# design.net
KiCad netlist of a schematic drawn in Altium Designer
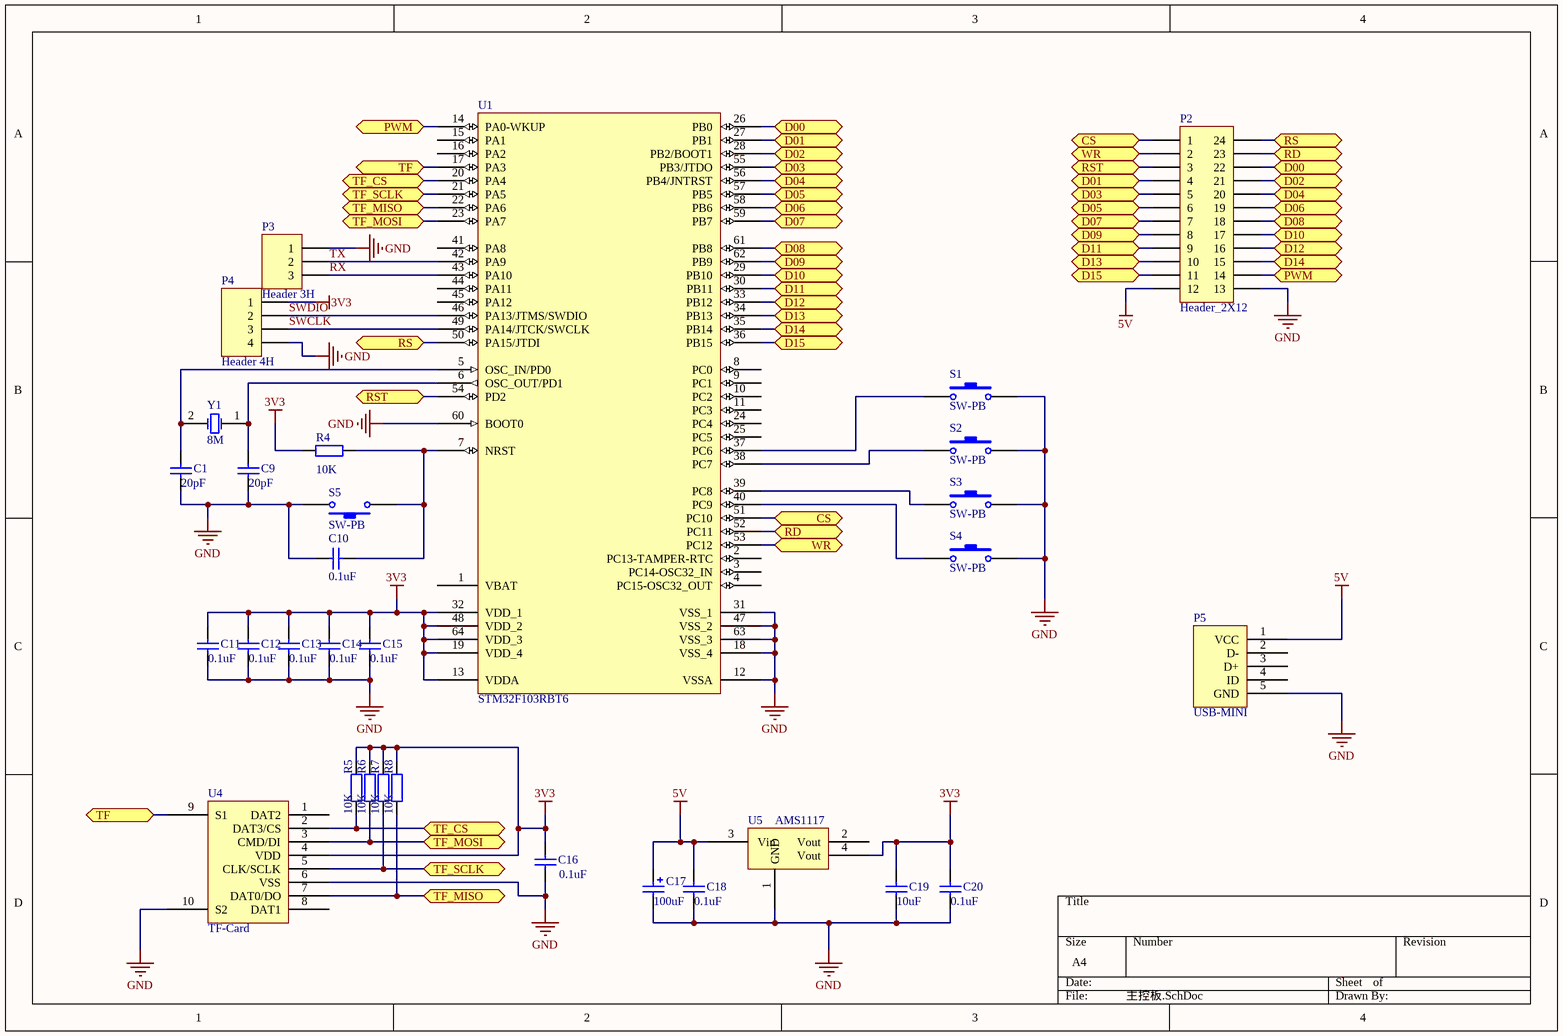
[diagram p0: 主控板.SchDoc]

(export (version "E")
  (design (tool "Eeschema 10.0.6"))
  (components
    (comp (ref "C1")
      (value "20pF")
      (footprint "6-0805_N")
      (description "Capacitor (Semiconductor SIM Model)")
      (fields (field (name "Comment") "Cap Semi") (field (name "PUBLISHER") "Altium Limited"))
      (libsource (lib "Miscellaneous Devices") (part "Cap Semi"))
    )
    (comp (ref "C9")
      (value "20pF")
      (footprint "6-0805_N")
      (description "Capacitor (Semiconductor SIM Model)")
      (fields (field (name "Comment") "Cap Semi") (field (name "PUBLISHER") "Altium Limited"))
      (libsource (lib "Miscellaneous Devices") (part "Cap Semi"))
    )
    (comp (ref "C10")
      (value "0.1uF")
      (footprint "1608[0603]")
      (description "Capacitor (Semiconductor SIM Model)")
      (fields (field (name "Comment") "Cap Semi") (field (name "PUBLISHER") "Altium Limited"))
      (libsource (lib "Miscellaneous Devices") (part "Cap Semi"))
    )
    (comp (ref "C11")
      (value "0.1uF")
      (footprint "1608[0603]")
      (description "Capacitor (Semiconductor SIM Model)")
      (fields (field (name "Comment") "Cap Semi") (field (name "PUBLISHER") "Altium Limited"))
      (libsource (lib "Miscellaneous Devices") (part "Cap Semi"))
    )
    (comp (ref "C12")
      (value "0.1uF")
      (footprint "1608[0603]")
      (description "Capacitor (Semiconductor SIM Model)")
      (fields (field (name "Comment") "Cap Semi") (field (name "PUBLISHER") "Altium Limited"))
      (libsource (lib "Miscellaneous Devices") (part "Cap Semi"))
    )
    (comp (ref "C13")
      (value "0.1uF")
      (footprint "1608[0603]")
      (description "Capacitor (Semiconductor SIM Model)")
      (fields (field (name "Comment") "Cap Semi") (field (name "PUBLISHER") "Altium Limited"))
      (libsource (lib "Miscellaneous Devices") (part "Cap Semi"))
    )
    (comp (ref "C14")
      (value "0.1uF")
      (footprint "1608[0603]")
      (description "Capacitor (Semiconductor SIM Model)")
      (fields (field (name "Comment") "Cap Semi") (field (name "PUBLISHER") "Altium Limited"))
      (libsource (lib "Miscellaneous Devices") (part "Cap Semi"))
    )
    (comp (ref "C15")
      (value "0.1uF")
      (footprint "1608[0603]")
      (description "Capacitor (Semiconductor SIM Model)")
      (fields (field (name "Comment") "Cap Semi") (field (name "PUBLISHER") "Altium Limited"))
      (libsource (lib "Miscellaneous Devices") (part "Cap Semi"))
    )
    (comp (ref "C16")
      (value "0.1uF")
      (footprint "1608[0603]")
      (description "Capacitor (Semiconductor SIM Model)")
      (fields (field (name "Comment") "Cap Semi") (field (name "PUBLISHER") "Altium Limited"))
      (libsource (lib "Miscellaneous Devices") (part "Cap Semi"))
    )
    (comp (ref "C17")
      (value "100uF")
      (footprint "3528")
      (description "Polarized Capacitor (Axial)")
      (fields (field (name "Comment") "Cap Pol2") (field (name "PUBLISHER") "Altium Limited"))
      (libsource (lib "Miscellaneous Devices") (part "Cap Pol2"))
    )
    (comp (ref "C18")
      (value "0.1uF")
      (footprint "1608[0603]")
      (description "Capacitor (Semiconductor SIM Model)")
      (fields (field (name "Comment") "Cap Semi") (field (name "PUBLISHER") "Altium Limited"))
      (libsource (lib "Miscellaneous Devices") (part "Cap Semi"))
    )
    (comp (ref "C19")
      (value "10uF")
      (footprint "1608[0603]")
      (description "Capacitor (Semiconductor SIM Model)")
      (fields (field (name "Comment") "Cap Semi") (field (name "PUBLISHER") "Altium Limited"))
      (libsource (lib "Miscellaneous Devices") (part "Cap Semi"))
    )
    (comp (ref "C20")
      (value "0.1uF")
      (footprint "1608[0603]")
      (description "Capacitor (Semiconductor SIM Model)")
      (fields (field (name "Comment") "Cap Semi") (field (name "PUBLISHER") "Altium Limited"))
      (libsource (lib "Miscellaneous Devices") (part "Cap Semi"))
    )
    (comp (ref "P2") (value "Header_2X12") (footprint "HDR2X12") (libsource (lib "元件") (part "Header_2X12")))
    (comp (ref "P3")
      (value "Header 3H")
      (footprint "HDR1X3H")
      (description "Header, 3-Pin, Right Angle")
      (fields (field (name "PUBLISHER") "Altium Limited"))
      (libsource (lib "Miscellaneous Connectors") (part "Header 3H"))
    )
    (comp (ref "P4")
      (value "Header 4H")
      (footprint "HDR1X4H")
      (description "Header, 4-Pin, Right Angle")
      (fields (field (name "PUBLISHER") "Altium Limited"))
      (libsource (lib "Miscellaneous Connectors") (part "Header 4H"))
    )
    (comp (ref "P5")
      (value "USB-MINI")
      (footprint "USB-MINI")
      (description "USB接口")
      (libsource (lib "元件") (part "USB-MINI"))
    )
    (comp (ref "R4")
      (value "10K")
      (footprint "1608[0603]")
      (description "Resistor")
      (fields (field (name "Comment") "Res2") (field (name "PUBLISHER") "Altium Limited"))
      (libsource (lib "") (part "Res2_1"))
    )
    (comp (ref "R5")
      (value "10K")
      (footprint "1608[0603]")
      (description "Resistor")
      (fields (field (name "Comment") "Res2") (field (name "PUBLISHER") "Altium Limited"))
      (libsource (lib "Miscellaneous Devices") (part "Res2"))
    )
    (comp (ref "R6")
      (value "10K")
      (footprint "1608[0603]")
      (description "Resistor")
      (fields (field (name "Comment") "Res2") (field (name "PUBLISHER") "Altium Limited"))
      (libsource (lib "Miscellaneous Devices") (part "Res2"))
    )
    (comp (ref "R7")
      (value "10K")
      (footprint "1608[0603]")
      (description "Resistor")
      (fields (field (name "Comment") "Res2") (field (name "PUBLISHER") "Altium Limited"))
      (libsource (lib "Miscellaneous Devices") (part "Res2"))
    )
    (comp (ref "R8")
      (value "10K")
      (footprint "1608[0603]")
      (description "Resistor")
      (fields (field (name "Comment") "Res2") (field (name "PUBLISHER") "Altium Limited"))
      (libsource (lib "Miscellaneous Devices") (part "Res2"))
    )
    (comp (ref "S1")
      (value "SW-PB")
      (footprint "SW-SMD")
      (description "Switch")
      (fields (field (name "PUBLISHER") "Altium Limited"))
      (libsource (lib "Miscellaneous Devices") (part "SW-PB"))
    )
    (comp (ref "S2")
      (value "SW-PB")
      (footprint "SW-SMD")
      (description "Switch")
      (fields (field (name "PUBLISHER") "Altium Limited"))
      (libsource (lib "Miscellaneous Devices") (part "SW-PB"))
    )
    (comp (ref "S3")
      (value "SW-PB")
      (footprint "SW-SMD")
      (description "Switch")
      (fields (field (name "PUBLISHER") "Altium Limited"))
      (libsource (lib "Miscellaneous Devices") (part "SW-PB"))
    )
    (comp (ref "S4")
      (value "SW-PB")
      (footprint "SW-SMD")
      (description "Switch")
      (fields (field (name "PUBLISHER") "Altium Limited"))
      (libsource (lib "Miscellaneous Devices") (part "SW-PB"))
    )
    (comp (ref "S5")
      (value "SW-PB")
      (footprint "SW-SMD")
      (description "Switch")
      (fields (field (name "PUBLISHER") "Altium Limited"))
      (libsource (lib "Miscellaneous Devices") (part "SW-PB"))
    )
    (comp (ref "U1")
      (value "STM32F103RBT6")
      (footprint "LQFP64_N")
      (description "STM32 ARM-based 32-bit MCU with 128 Kbytes Flash, 64-pin LQFP, Industrial Temperature")
      (fields (field (name "PUBLISHER") "Altium Limited"))
      (libsource (lib "ST Microcontroller 32-Bit STM32") (part "STM32F103RBT6"))
    )
    (comp (ref "U4")
      (value "TF-Card")
      (footprint "TF-Card")
      (description "TF存储卡")
      (libsource (lib "元件") (part "TF-Card"))
    )
    (comp (ref "U5")
      (value "AMS1117")
      (footprint "SOT223")
      (description "稳压IC")
      (libsource (lib "元件") (part "AMS1117"))
    )
    (comp (ref "Y1")
      (value "8M")
      (footprint "XTAL - duplicate")
      (description "Crystal Oscillator")
      (fields (field (name "PUBLISHER") "Altium Limited"))
      (libsource (lib "Miscellaneous Devices") (part "XTAL"))
    )
  )
  (nets
    (net (code "1") (name "/CS") (class "Default")
      (node (ref "P2") (pin "1") (pinfunction "1_1") (pintype "passive"))
      (node (ref "U1") (pin "51") (pinfunction "PC10_51") (pintype "bidirectional"))
    )
    (net (code "2") (name "/D00") (class "Default")
      (node (ref "P2") (pin "22") (pinfunction "22_22") (pintype "passive"))
      (node (ref "U1") (pin "26") (pinfunction "PB0_26") (pintype "bidirectional"))
    )
    (net (code "3") (name "/D01") (class "Default")
      (node (ref "P2") (pin "4") (pinfunction "4_4") (pintype "passive"))
      (node (ref "U1") (pin "27") (pinfunction "PB1_27") (pintype "bidirectional"))
    )
    (net (code "4") (name "/D02") (class "Default")
      (node (ref "P2") (pin "21") (pinfunction "21_21") (pintype "passive"))
      (node (ref "U1") (pin "28") (pinfunction "PB2/BOOT1_28") (pintype "bidirectional"))
    )
    (net (code "5") (name "/D03") (class "Default")
      (node (ref "P2") (pin "5") (pinfunction "5_5") (pintype "passive"))
      (node (ref "U1") (pin "55") (pinfunction "PB3/JTDO_55") (pintype "bidirectional"))
    )
    (net (code "6") (name "/D04") (class "Default")
      (node (ref "P2") (pin "20") (pinfunction "20_20") (pintype "passive"))
      (node (ref "U1") (pin "56") (pinfunction "PB4/JNTRST_56") (pintype "bidirectional"))
    )
    (net (code "7") (name "/D05") (class "Default")
      (node (ref "P2") (pin "6") (pinfunction "6_6") (pintype "passive"))
      (node (ref "U1") (pin "57") (pinfunction "PB5_57") (pintype "bidirectional"))
    )
    (net (code "8") (name "/D06") (class "Default")
      (node (ref "P2") (pin "19") (pinfunction "19_19") (pintype "passive"))
      (node (ref "U1") (pin "58") (pinfunction "PB6_58") (pintype "bidirectional"))
    )
    (net (code "9") (name "/D07") (class "Default")
      (node (ref "P2") (pin "7") (pinfunction "7_7") (pintype "passive"))
      (node (ref "U1") (pin "59") (pinfunction "PB7_59") (pintype "bidirectional"))
    )
    (net (code "10") (name "/D08") (class "Default")
      (node (ref "P2") (pin "18") (pinfunction "18_18") (pintype "passive"))
      (node (ref "U1") (pin "61") (pinfunction "PB8_61") (pintype "bidirectional"))
    )
    (net (code "11") (name "/D09") (class "Default")
      (node (ref "P2") (pin "8") (pinfunction "8_8") (pintype "passive"))
      (node (ref "U1") (pin "62") (pinfunction "PB9_62") (pintype "bidirectional"))
    )
    (net (code "12") (name "/D10") (class "Default")
      (node (ref "P2") (pin "17") (pinfunction "17_17") (pintype "passive"))
      (node (ref "U1") (pin "29") (pinfunction "PB10_29") (pintype "bidirectional"))
    )
    (net (code "13") (name "/D11") (class "Default")
      (node (ref "P2") (pin "9") (pinfunction "9_9") (pintype "passive"))
      (node (ref "U1") (pin "30") (pinfunction "PB11_30") (pintype "bidirectional"))
    )
    (net (code "14") (name "/D12") (class "Default")
      (node (ref "P2") (pin "16") (pinfunction "16_16") (pintype "passive"))
      (node (ref "U1") (pin "33") (pinfunction "PB12_33") (pintype "bidirectional"))
    )
    (net (code "15") (name "/D13") (class "Default")
      (node (ref "P2") (pin "10") (pinfunction "10_10") (pintype "passive"))
      (node (ref "U1") (pin "34") (pinfunction "PB13_34") (pintype "bidirectional"))
    )
    (net (code "16") (name "/D14") (class "Default")
      (node (ref "P2") (pin "15") (pinfunction "15_15") (pintype "passive"))
      (node (ref "U1") (pin "35") (pinfunction "PB14_35") (pintype "bidirectional"))
    )
    (net (code "17") (name "/D15") (class "Default")
      (node (ref "P2") (pin "11") (pinfunction "11_11") (pintype "passive"))
      (node (ref "U1") (pin "36") (pinfunction "PB15_36") (pintype "bidirectional"))
    )
    (net (code "18") (name "/PWM") (class "Default")
      (node (ref "P2") (pin "14") (pinfunction "14_14") (pintype "passive"))
      (node (ref "U1") (pin "14") (pinfunction "PA0-WKUP_14") (pintype "bidirectional"))
    )
    (net (code "19") (name "/RD") (class "Default")
      (node (ref "P2") (pin "23") (pinfunction "23_23") (pintype "passive"))
      (node (ref "U1") (pin "52") (pinfunction "PC11_52") (pintype "bidirectional"))
    )
    (net (code "20") (name "/RS") (class "Default")
      (node (ref "P2") (pin "24") (pinfunction "24_24") (pintype "passive"))
      (node (ref "U1") (pin "50") (pinfunction "PA15/JTDI_50") (pintype "bidirectional"))
    )
    (net (code "21") (name "/RST") (class "Default")
      (node (ref "P2") (pin "3") (pinfunction "3_3") (pintype "passive"))
      (node (ref "U1") (pin "54") (pinfunction "PD2_54") (pintype "bidirectional"))
    )
    (net (code "22") (name "/RX") (class "Default")
      (node (ref "P3") (pin "3") (pinfunction "3_3") (pintype "passive"))
      (node (ref "U1") (pin "43") (pinfunction "PA10_43") (pintype "bidirectional"))
    )
    (net (code "23") (name "/SWCLK") (class "Default")
      (node (ref "P4") (pin "3") (pinfunction "3_3") (pintype "passive"))
      (node (ref "U1") (pin "49") (pinfunction "PA14/JTCK/SWCLK_49") (pintype "bidirectional"))
    )
    (net (code "24") (name "/SWDIO") (class "Default")
      (node (ref "P4") (pin "2") (pinfunction "2_2") (pintype "passive"))
      (node (ref "U1") (pin "46") (pinfunction "PA13/JTMS/SWDIO_46") (pintype "bidirectional"))
    )
    (net (code "25") (name "/TF") (class "Default")
      (node (ref "U1") (pin "17") (pinfunction "PA3_17") (pintype "bidirectional"))
      (node (ref "U4") (pin "9") (pinfunction "S1_9") (pintype "passive"))
    )
    (net (code "26") (name "/TF_CS") (class "Default")
      (node (ref "R5") (pin "1") (pinfunction "1_1") (pintype "passive"))
      (node (ref "U1") (pin "20") (pinfunction "PA4_20") (pintype "bidirectional"))
      (node (ref "U4") (pin "2") (pinfunction "DAT3/CS_2") (pintype "passive"))
    )
    (net (code "27") (name "/TF_MISO") (class "Default")
      (node (ref "R8") (pin "1") (pinfunction "1_1") (pintype "passive"))
      (node (ref "U1") (pin "22") (pinfunction "PA6_22") (pintype "bidirectional"))
      (node (ref "U4") (pin "7") (pinfunction "DAT0/DO_7") (pintype "passive"))
    )
    (net (code "28") (name "/TF_MOSI") (class "Default")
      (node (ref "R6") (pin "1") (pinfunction "1_1") (pintype "passive"))
      (node (ref "U1") (pin "23") (pinfunction "PA7_23") (pintype "bidirectional"))
      (node (ref "U4") (pin "3") (pinfunction "CMD/DI_3") (pintype "passive"))
    )
    (net (code "29") (name "/TF_SCLK") (class "Default")
      (node (ref "R7") (pin "1") (pinfunction "1_1") (pintype "passive"))
      (node (ref "U1") (pin "21") (pinfunction "PA5_21") (pintype "bidirectional"))
      (node (ref "U4") (pin "5") (pinfunction "CLK/SCLK_5") (pintype "passive"))
    )
    (net (code "30") (name "/TX") (class "Default")
      (node (ref "P3") (pin "2") (pinfunction "2_2") (pintype "passive"))
      (node (ref "U1") (pin "42") (pinfunction "PA9_42") (pintype "bidirectional"))
    )
    (net (code "31") (name "/WR") (class "Default")
      (node (ref "P2") (pin "2") (pinfunction "2_2") (pintype "passive"))
      (node (ref "U1") (pin "53") (pinfunction "PC12_53") (pintype "bidirectional"))
    )
    (net (code "32") (name "3V3") (class "Default")
      (node (ref "C11") (pin "2") (pinfunction "2_2") (pintype "passive"))
      (node (ref "C12") (pin "2") (pinfunction "2_2") (pintype "passive"))
      (node (ref "C13") (pin "2") (pinfunction "2_2") (pintype "passive"))
      (node (ref "C14") (pin "2") (pinfunction "2_2") (pintype "passive"))
      (node (ref "C15") (pin "2") (pinfunction "2_2") (pintype "passive"))
      (node (ref "C16") (pin "2") (pinfunction "2_2") (pintype "passive"))
      (node (ref "C19") (pin "2") (pinfunction "2_2") (pintype "passive"))
      (node (ref "C20") (pin "2") (pinfunction "2_2") (pintype "passive"))
      (node (ref "P4") (pin "1") (pinfunction "1_1") (pintype "passive"))
      (node (ref "R4") (pin "1") (pinfunction "1_1") (pintype "passive"))
      (node (ref "R5") (pin "2") (pinfunction "2_2") (pintype "passive"))
      (node (ref "R6") (pin "2") (pinfunction "2_2") (pintype "passive"))
      (node (ref "R7") (pin "2") (pinfunction "2_2") (pintype "passive"))
      (node (ref "R8") (pin "2") (pinfunction "2_2") (pintype "passive"))
      (node (ref "U1") (pin "13") (pinfunction "VDDA_13") (pintype "power_in"))
      (node (ref "U1") (pin "19") (pinfunction "VDD_4_19") (pintype "power_in"))
      (node (ref "U1") (pin "32") (pinfunction "VDD_1_32") (pintype "power_in"))
      (node (ref "U1") (pin "48") (pinfunction "VDD_2_48") (pintype "power_in"))
      (node (ref "U1") (pin "64") (pinfunction "VDD_3_64") (pintype "power_in"))
      (node (ref "U4") (pin "4") (pinfunction "VDD_4") (pintype "passive"))
      (node (ref "U5") (pin "4") (pinfunction "Vout_4") (pintype "passive"))
    )
    (net (code "33") (name "5V") (class "Default")
      (node (ref "C17") (pin "1") (pinfunction "1_1") (pintype "passive"))
      (node (ref "C18") (pin "2") (pinfunction "2_2") (pintype "passive"))
      (node (ref "P2") (pin "12") (pinfunction "12_12") (pintype "passive"))
      (node (ref "P5") (pin "1") (pinfunction "VCC_1") (pintype "passive"))
      (node (ref "U5") (pin "3") (pinfunction "Vin_3") (pintype "passive"))
    )
    (net (code "34") (name "GND") (class "Default")
      (node (ref "C1") (pin "1") (pinfunction "1_1") (pintype "passive"))
      (node (ref "C10") (pin "2") (pinfunction "2_2") (pintype "passive"))
      (node (ref "C11") (pin "1") (pinfunction "1_1") (pintype "passive"))
      (node (ref "C12") (pin "1") (pinfunction "1_1") (pintype "passive"))
      (node (ref "C13") (pin "1") (pinfunction "1_1") (pintype "passive"))
      (node (ref "C14") (pin "1") (pinfunction "1_1") (pintype "passive"))
      (node (ref "C15") (pin "1") (pinfunction "1_1") (pintype "passive"))
      (node (ref "C16") (pin "1") (pinfunction "1_1") (pintype "passive"))
      (node (ref "C17") (pin "2") (pinfunction "2_2") (pintype "passive"))
      (node (ref "C18") (pin "1") (pinfunction "1_1") (pintype "passive"))
      (node (ref "C19") (pin "1") (pinfunction "1_1") (pintype "passive"))
      (node (ref "C20") (pin "1") (pinfunction "1_1") (pintype "passive"))
      (node (ref "C9") (pin "1") (pinfunction "1_1") (pintype "passive"))
      (node (ref "P2") (pin "13") (pinfunction "13_13") (pintype "passive"))
      (node (ref "P3") (pin "1") (pinfunction "1_1") (pintype "passive"))
      (node (ref "P4") (pin "4") (pinfunction "4_4") (pintype "passive"))
      (node (ref "P5") (pin "5") (pinfunction "GND_5") (pintype "passive"))
      (node (ref "S1") (pin "2") (pinfunction "2_2") (pintype "passive"))
      (node (ref "S2") (pin "2") (pinfunction "2_2") (pintype "passive"))
      (node (ref "S3") (pin "2") (pinfunction "2_2") (pintype "passive"))
      (node (ref "S4") (pin "2") (pinfunction "2_2") (pintype "passive"))
      (node (ref "S5") (pin "2") (pinfunction "2_2") (pintype "passive"))
      (node (ref "U1") (pin "12") (pinfunction "VSSA_12") (pintype "power_in"))
      (node (ref "U1") (pin "18") (pinfunction "VSS_4_18") (pintype "power_in"))
      (node (ref "U1") (pin "31") (pinfunction "VSS_1_31") (pintype "power_in"))
      (node (ref "U1") (pin "47") (pinfunction "VSS_2_47") (pintype "power_in"))
      (node (ref "U1") (pin "60") (pinfunction "BOOT0_60") (pintype "input"))
      (node (ref "U1") (pin "63") (pinfunction "VSS_3_63") (pintype "power_in"))
      (node (ref "U4") (pin "10") (pinfunction "S2_10") (pintype "passive"))
      (node (ref "U4") (pin "6") (pinfunction "VSS_6") (pintype "passive"))
      (node (ref "U5") (pin "1") (pinfunction "GND_1") (pintype "passive"))
    )
    (net (code "35") (name "Net-(U1-NRST)") (class "Default")
      (node (ref "C10") (pin "1") (pinfunction "1_1") (pintype "passive"))
      (node (ref "R4") (pin "2") (pinfunction "2_2") (pintype "passive"))
      (node (ref "S5") (pin "1") (pinfunction "1_1") (pintype "passive"))
      (node (ref "U1") (pin "7") (pinfunction "NRST_7") (pintype "bidirectional"))
    )
    (net (code "36") (name "Net-(U1-OSC_IN{slash}PD0)") (class "Default")
      (node (ref "C1") (pin "2") (pinfunction "2_2") (pintype "passive"))
      (node (ref "U1") (pin "5") (pinfunction "OSC_IN/PD0_5") (pintype "input"))
      (node (ref "Y1") (pin "2") (pinfunction "OSC2_2") (pintype "passive"))
    )
    (net (code "37") (name "Net-(U1-OSC_OUT{slash}PD1)") (class "Default")
      (node (ref "C9") (pin "2") (pinfunction "2_2") (pintype "passive"))
      (node (ref "U1") (pin "6") (pinfunction "OSC_OUT/PD1_6") (pintype "output"))
      (node (ref "Y1") (pin "1") (pinfunction "OSC1_1") (pintype "passive"))
    )
    (net (code "38") (name "Net-(U1-PC6)") (class "Default")
      (node (ref "S1") (pin "1") (pinfunction "1_1") (pintype "passive"))
      (node (ref "U1") (pin "37") (pinfunction "PC6_37") (pintype "bidirectional"))
    )
    (net (code "39") (name "Net-(U1-PC7)") (class "Default")
      (node (ref "S2") (pin "1") (pinfunction "1_1") (pintype "passive"))
      (node (ref "U1") (pin "38") (pinfunction "PC7_38") (pintype "bidirectional"))
    )
    (net (code "40") (name "Net-(U1-PC8)") (class "Default")
      (node (ref "S3") (pin "1") (pinfunction "1_1") (pintype "passive"))
      (node (ref "U1") (pin "39") (pinfunction "PC8_39") (pintype "bidirectional"))
    )
    (net (code "41") (name "Net-(U1-PC9)") (class "Default")
      (node (ref "S4") (pin "1") (pinfunction "1_1") (pintype "passive"))
      (node (ref "U1") (pin "40") (pinfunction "PC9_40") (pintype "bidirectional"))
    )
    (net (code "42") (name "unconnected-(P5-D+-Pad3)") (class "Default")
      (node (ref "P5") (pin "3") (pinfunction "D+_3") (pintype "passive"))
    )
    (net (code "43") (name "unconnected-(P5-D--Pad2)") (class "Default")
      (node (ref "P5") (pin "2") (pinfunction "D-_2") (pintype "passive"))
    )
    (net (code "44") (name "unconnected-(P5-ID-Pad4)") (class "Default")
      (node (ref "P5") (pin "4") (pinfunction "ID_4") (pintype "passive"))
    )
    (net (code "45") (name "unconnected-(U1-PA1-Pad15)") (class "Default")
      (node (ref "U1") (pin "15") (pinfunction "PA1_15") (pintype "bidirectional"))
    )
    (net (code "46") (name "unconnected-(U1-PA2-Pad16)") (class "Default")
      (node (ref "U1") (pin "16") (pinfunction "PA2_16") (pintype "bidirectional"))
    )
    (net (code "47") (name "unconnected-(U1-PA8-Pad41)") (class "Default")
      (node (ref "U1") (pin "41") (pinfunction "PA8_41") (pintype "bidirectional"))
    )
    (net (code "48") (name "unconnected-(U1-PA11-Pad44)") (class "Default")
      (node (ref "U1") (pin "44") (pinfunction "PA11_44") (pintype "bidirectional"))
    )
    (net (code "49") (name "unconnected-(U1-PA12-Pad45)") (class "Default")
      (node (ref "U1") (pin "45") (pinfunction "PA12_45") (pintype "bidirectional"))
    )
    (net (code "50") (name "unconnected-(U1-PC0-Pad8)") (class "Default")
      (node (ref "U1") (pin "8") (pinfunction "PC0_8") (pintype "bidirectional"))
    )
    (net (code "51") (name "unconnected-(U1-PC1-Pad9)") (class "Default")
      (node (ref "U1") (pin "9") (pinfunction "PC1_9") (pintype "bidirectional"))
    )
    (net (code "52") (name "unconnected-(U1-PC2-Pad10)") (class "Default")
      (node (ref "U1") (pin "10") (pinfunction "PC2_10") (pintype "bidirectional"))
    )
    (net (code "53") (name "unconnected-(U1-PC3-Pad11)") (class "Default")
      (node (ref "U1") (pin "11") (pinfunction "PC3_11") (pintype "bidirectional"))
    )
    (net (code "54") (name "unconnected-(U1-PC4-Pad24)") (class "Default")
      (node (ref "U1") (pin "24") (pinfunction "PC4_24") (pintype "bidirectional"))
    )
    (net (code "55") (name "unconnected-(U1-PC5-Pad25)") (class "Default")
      (node (ref "U1") (pin "25") (pinfunction "PC5_25") (pintype "bidirectional"))
    )
    (net (code "56") (name "unconnected-(U1-PC13-TAMPER-RTC-Pad2)") (class "Default")
      (node (ref "U1") (pin "2") (pinfunction "PC13-TAMPER-RTC_2") (pintype "bidirectional"))
    )
    (net (code "57") (name "unconnected-(U1-PC14-OSC32_IN-Pad3)") (class "Default")
      (node (ref "U1") (pin "3") (pinfunction "PC14-OSC32_IN_3") (pintype "bidirectional"))
    )
    (net (code "58") (name "unconnected-(U1-PC15-OSC32_OUT-Pad4)") (class "Default")
      (node (ref "U1") (pin "4") (pinfunction "PC15-OSC32_OUT_4") (pintype "bidirectional"))
    )
    (net (code "59") (name "unconnected-(U1-VBAT-Pad1)") (class "Default")
      (node (ref "U1") (pin "1") (pinfunction "VBAT_1") (pintype "power_in"))
    )
    (net (code "60") (name "unconnected-(U4-DAT1-Pad8)") (class "Default")
      (node (ref "U4") (pin "8") (pinfunction "DAT1_8") (pintype "passive"))
    )
    (net (code "61") (name "unconnected-(U4-DAT2-Pad1)") (class "Default")
      (node (ref "U4") (pin "1") (pinfunction "DAT2_1") (pintype "passive"))
    )
    (net (code "62") (name "unconnected-(U5-Vout-Pad2)") (class "Default")
      (node (ref "U5") (pin "2") (pinfunction "Vout_2") (pintype "power_in"))
    )
  )
)
